# Sheet_power_1.net
KiCad netlist of a schematic drawn in Altium Designer
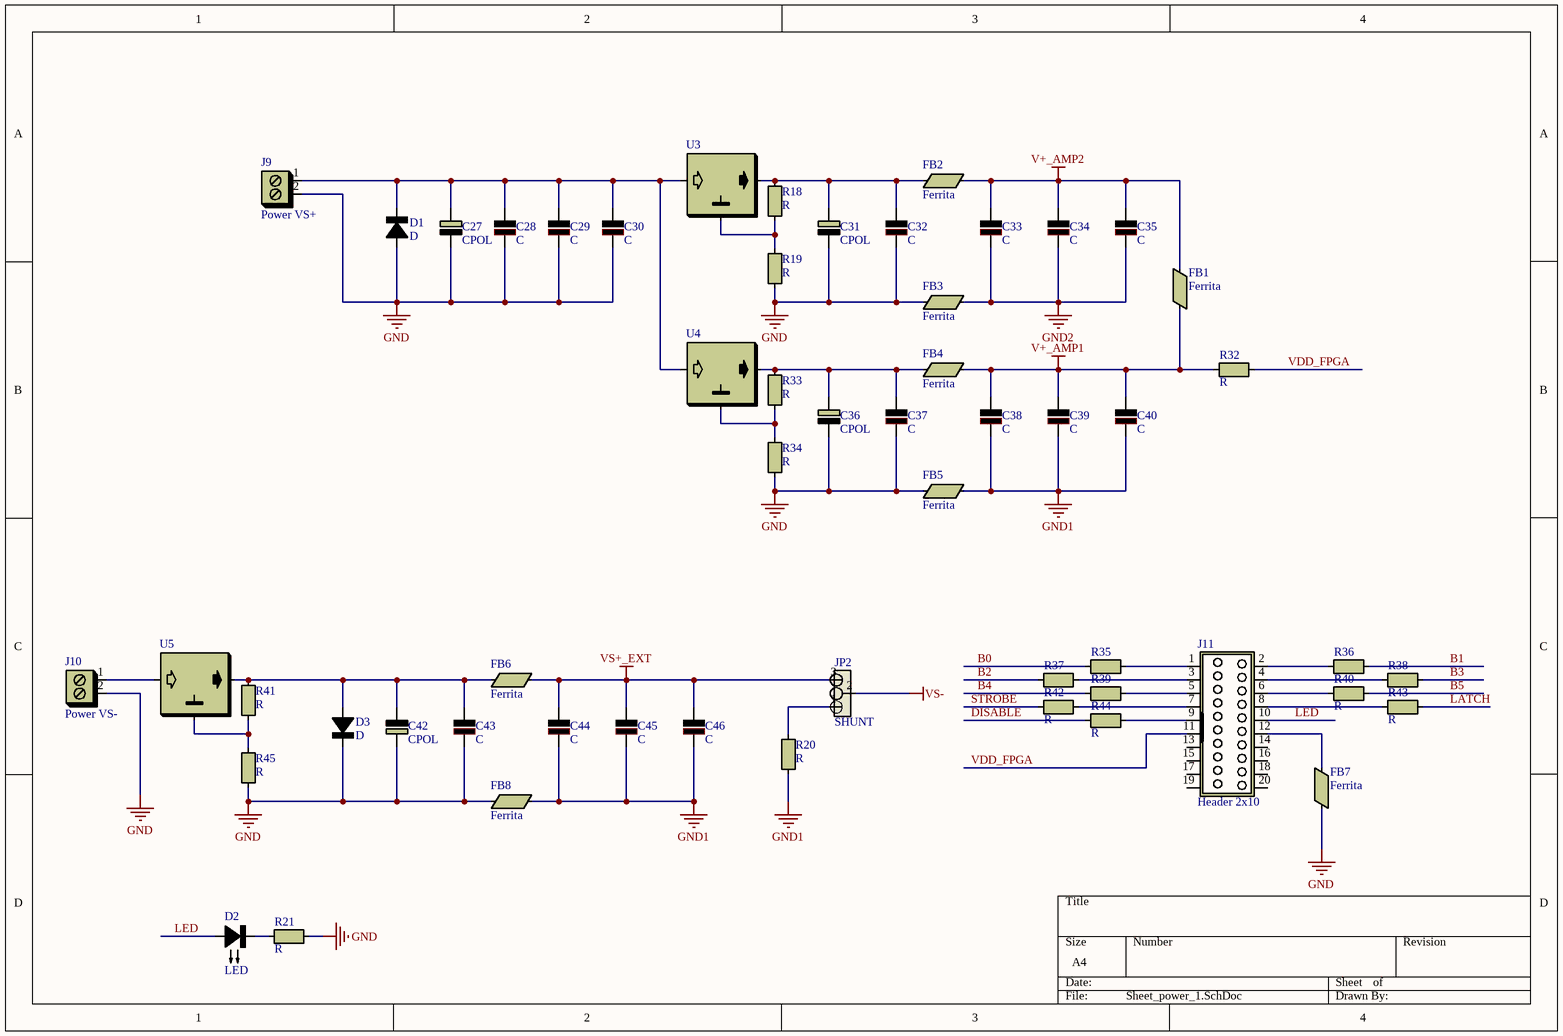
[diagram p0: Sheet_power_1.SchDoc]

(export (version "E")
  (design (tool "Eeschema 10.0.6"))
  (components
    (comp (ref "C27") (value "CPOL") (footprint "C_SMD_5.0 x 5.4") (libsource (lib "") (part "CPOL_1")))
    (comp (ref "C28") (value "C") (footprint "C_0805") (libsource (lib "Alberto_Sch") (part "C")))
    (comp (ref "C29") (value "C") (footprint "C_0805") (libsource (lib "Alberto_Sch") (part "C")))
    (comp (ref "C30") (value "C") (footprint "C_0805") (libsource (lib "Alberto_Sch") (part "C")))
    (comp (ref "C31") (value "CPOL") (footprint "C_SMD_5.0 x 5.4") (libsource (lib "") (part "CPOL_1")))
    (comp (ref "C32") (value "C") (footprint "C_0805") (libsource (lib "Alberto_Sch") (part "C")))
    (comp (ref "C33") (value "C") (footprint "C_0805") (libsource (lib "Alberto_Sch") (part "C")))
    (comp (ref "C34") (value "C") (footprint "C_0805") (libsource (lib "Alberto_Sch") (part "C")))
    (comp (ref "C35") (value "C") (footprint "C_0805") (libsource (lib "Alberto_Sch") (part "C")))
    (comp (ref "C36") (value "CPOL") (footprint "C_SMD_5.0 x 5.4") (libsource (lib "") (part "CPOL_1")))
    (comp (ref "C37") (value "C") (footprint "C_0805") (libsource (lib "Alberto_Sch") (part "C")))
    (comp (ref "C38") (value "C") (footprint "C_0805") (libsource (lib "Alberto_Sch") (part "C")))
    (comp (ref "C39") (value "C") (footprint "C_0805") (libsource (lib "Alberto_Sch") (part "C")))
    (comp (ref "C40") (value "C") (footprint "C_0805") (libsource (lib "Alberto_Sch") (part "C")))
    (comp (ref "C42")
      (value "CPOL")
      (footprint "C_SMD_5.0 x 5.4")
      (libsource (lib "Alberto_Sch") (part "CPOL"))
    )
    (comp (ref "C43") (value "C") (footprint "C_0805") (libsource (lib "Alberto_Sch") (part "C")))
    (comp (ref "C44") (value "C") (footprint "C_0805") (libsource (lib "Alberto_Sch") (part "C")))
    (comp (ref "C45") (value "C") (footprint "C_0805") (libsource (lib "Alberto_Sch") (part "C")))
    (comp (ref "C46") (value "C") (footprint "C_0805") (libsource (lib "Alberto_Sch") (part "C")))
    (comp (ref "D1") (value "D") (footprint "DZENER_0805") (libsource (lib "") (part "D_1")))
    (comp (ref "D2") (value "LED") (footprint "LED_0805") (libsource (lib "Alberto_Sch") (part "LED")))
    (comp (ref "D3") (value "D") (footprint "DZENER_0805") (libsource (lib "Alberto_Sch") (part "D")))
    (comp (ref "FB1") (value "Ferrita") (footprint "R_0805") (libsource (lib "Alberto_Sch") (part "Ferrita")))
    (comp (ref "FB2") (value "Ferrita") (footprint "R_0805") (libsource (lib "Alberto_Sch") (part "Ferrita")))
    (comp (ref "FB3") (value "Ferrita") (footprint "R_0805") (libsource (lib "Alberto_Sch") (part "Ferrita")))
    (comp (ref "FB4") (value "Ferrita") (footprint "R_0805") (libsource (lib "Alberto_Sch") (part "Ferrita")))
    (comp (ref "FB5") (value "Ferrita") (footprint "R_0805") (libsource (lib "Alberto_Sch") (part "Ferrita")))
    (comp (ref "FB6") (value "Ferrita") (footprint "R_0805") (libsource (lib "Alberto_Sch") (part "Ferrita")))
    (comp (ref "FB7") (value "Ferrita") (footprint "R_0805") (libsource (lib "Alberto_Sch") (part "Ferrita")))
    (comp (ref "FB8") (value "Ferrita") (footprint "R_0805") (libsource (lib "Alberto_Sch") (part "Ferrita")))
    (comp (ref "J9")
      (value "Power VS+")
      (footprint "Borna_PT_2")
      (libsource (lib "Alberto_Sch") (part "BORNA_2"))
    )
    (comp (ref "J10")
      (value "Power VS-")
      (footprint "Borna_PT_2")
      (libsource (lib "Alberto_Sch") (part "BORNA_2"))
    )
    (comp (ref "J11") (value "Header 2x10") (libsource (lib "Alberto_Sch") (part "Header 2x10")))
    (comp (ref "JP2")
      (value "SHUNT")
      (footprint "JUMPER_2,54_3")
      (libsource (lib "Alberto_Sch") (part "SHUNT"))
    )
    (comp (ref "R18") (value "R") (footprint "R_0603") (libsource (lib "Alberto_Sch") (part "R")))
    (comp (ref "R19") (value "R") (footprint "R_0603") (libsource (lib "Alberto_Sch") (part "R")))
    (comp (ref "R20") (value "R") (footprint "R_0603") (libsource (lib "Alberto_Sch") (part "R")))
    (comp (ref "R21") (value "R") (footprint "R_0603") (libsource (lib "") (part "R_1")))
    (comp (ref "R32") (value "R") (footprint "R_0603") (libsource (lib "") (part "R_1")))
    (comp (ref "R33") (value "R") (footprint "R_0603") (libsource (lib "Alberto_Sch") (part "R")))
    (comp (ref "R34") (value "R") (footprint "R_0603") (libsource (lib "Alberto_Sch") (part "R")))
    (comp (ref "R35") (value "R") (footprint "R_0603") (libsource (lib "") (part "R_1")))
    (comp (ref "R36") (value "R") (footprint "R_0603") (libsource (lib "") (part "R_1")))
    (comp (ref "R37") (value "R") (footprint "R_0603") (libsource (lib "") (part "R_1")))
    (comp (ref "R38") (value "R") (footprint "R_0603") (libsource (lib "") (part "R_1")))
    (comp (ref "R39") (value "R") (footprint "R_0603") (libsource (lib "") (part "R_1")))
    (comp (ref "R40") (value "R") (footprint "R_0603") (libsource (lib "") (part "R_1")))
    (comp (ref "R41") (value "R") (footprint "R_0603") (libsource (lib "Alberto_Sch") (part "R")))
    (comp (ref "R42") (value "R") (footprint "R_0603") (libsource (lib "") (part "R_1")))
    (comp (ref "R43") (value "R") (footprint "R_0603") (libsource (lib "") (part "R_1")))
    (comp (ref "R44") (value "R") (footprint "R_0603") (libsource (lib "") (part "R_1")))
    (comp (ref "R45") (value "R") (footprint "R_0603") (libsource (lib "Alberto_Sch") (part "R")))
    (comp (ref "U3")
      (value "VOLTAGE_REGULATOR_3")
      (footprint "REG_DPAK")
      (libsource (lib "Alberto_Sch") (part "VOLTAGE_REGULATOR_3"))
    )
    (comp (ref "U4")
      (value "VOLTAGE_REGULATOR_3")
      (footprint "REG_DPAK")
      (libsource (lib "Alberto_Sch") (part "VOLTAGE_REGULATOR_3"))
    )
    (comp (ref "U5")
      (value "VOLTAGE_REGULATOR_3")
      (footprint "REG_DPAK")
      (libsource (lib "Alberto_Sch") (part "VOLTAGE_REGULATOR_3"))
    )
  )
  (nets
    (net (code "1") (name "/B0") (class "Default") (node (ref "R35") (pin "1") (pintype "passive")))
    (net (code "2") (name "/B1") (class "Default") (node (ref "R36") (pin "2") (pintype "passive")))
    (net (code "3") (name "/B2") (class "Default") (node (ref "R37") (pin "1") (pintype "passive")))
    (net (code "4") (name "/B3") (class "Default") (node (ref "R38") (pin "2") (pintype "passive")))
    (net (code "5") (name "/B4") (class "Default") (node (ref "R39") (pin "1") (pintype "passive")))
    (net (code "6") (name "/B5") (class "Default") (node (ref "R40") (pin "2") (pintype "passive")))
    (net (code "7") (name "/LATCH") (class "Default") (node (ref "R43") (pin "2") (pintype "passive")))
    (net (code "8") (name "/LED") (class "Default")
      (node (ref "D2") (pin "A") (pintype "passive"))
      (node (ref "J11") (pin "10") (pinfunction "10_10") (pintype "passive"))
    )
    (net (code "9") (name "/STROBE") (class "Default") (node (ref "R42") (pin "1") (pintype "passive")))
    (net (code "10") (name "/VDD_FPGA") (class "Default")
      (node (ref "J11") (pin "11") (pinfunction "11_11") (pintype "passive"))
      (node (ref "R32") (pin "2") (pintype "passive"))
    )
    (net (code "11") (name "/~{DISABLE}") (class "Default") (node (ref "R44") (pin "1") (pintype "passive")))
    (net (code "12") (name "GND") (class "Default")
      (node (ref "C27") (pin "1") (pintype "passive"))
      (node (ref "C28") (pin "2") (pintype "passive"))
      (node (ref "C29") (pin "2") (pintype "passive"))
      (node (ref "C30") (pin "2") (pintype "passive"))
      (node (ref "C31") (pin "1") (pintype "passive"))
      (node (ref "C32") (pin "2") (pintype "passive"))
      (node (ref "C36") (pin "1") (pintype "passive"))
      (node (ref "C37") (pin "2") (pintype "passive"))
      (node (ref "C42") (pin "2") (pintype "passive"))
      (node (ref "C43") (pin "2") (pintype "passive"))
      (node (ref "D1") (pin "A") (pintype "passive"))
      (node (ref "D3") (pin "K") (pintype "passive"))
      (node (ref "FB3") (pin "2") (pintype "passive"))
      (node (ref "FB5") (pin "2") (pintype "passive"))
      (node (ref "FB7") (pin "1") (pintype "passive"))
      (node (ref "FB8") (pin "2") (pintype "passive"))
      (node (ref "J10") (pin "2") (pintype "passive"))
      (node (ref "J9") (pin "2") (pintype "passive"))
      (node (ref "R19") (pin "2") (pintype "passive"))
      (node (ref "R21") (pin "2") (pintype "passive"))
      (node (ref "R34") (pin "2") (pintype "passive"))
      (node (ref "R45") (pin "2") (pintype "passive"))
    )
    (net (code "13") (name "GND1") (class "Default")
      (node (ref "C38") (pin "2") (pintype "passive"))
      (node (ref "C39") (pin "2") (pintype "passive"))
      (node (ref "C40") (pin "2") (pintype "passive"))
      (node (ref "C44") (pin "2") (pintype "passive"))
      (node (ref "C45") (pin "2") (pintype "passive"))
      (node (ref "C46") (pin "2") (pintype "passive"))
      (node (ref "FB5") (pin "1") (pintype "passive"))
      (node (ref "FB8") (pin "1") (pintype "passive"))
      (node (ref "R20") (pin "2") (pintype "passive"))
    )
    (net (code "14") (name "GND2") (class "Default")
      (node (ref "C33") (pin "2") (pintype "passive"))
      (node (ref "C34") (pin "2") (pintype "passive"))
      (node (ref "C35") (pin "2") (pintype "passive"))
      (node (ref "FB3") (pin "1") (pintype "passive"))
    )
    (net (code "15") (name "Net-(C27-Pad2)") (class "Default")
      (node (ref "C27") (pin "2") (pintype "passive"))
      (node (ref "C28") (pin "1") (pintype "passive"))
      (node (ref "C29") (pin "1") (pintype "passive"))
      (node (ref "C30") (pin "1") (pintype "passive"))
      (node (ref "D1") (pin "K") (pintype "passive"))
      (node (ref "J9") (pin "1") (pintype "passive"))
      (node (ref "U3") (pin "IN") (pintype "passive"))
      (node (ref "U4") (pin "IN") (pintype "passive"))
    )
    (net (code "16") (name "Net-(C31-Pad2)") (class "Default")
      (node (ref "C31") (pin "2") (pintype "passive"))
      (node (ref "C32") (pin "1") (pintype "passive"))
      (node (ref "FB2") (pin "2") (pintype "passive"))
      (node (ref "R18") (pin "1") (pintype "passive"))
      (node (ref "U3") (pin "OUT") (pintype "passive"))
    )
    (net (code "17") (name "Net-(C36-Pad2)") (class "Default")
      (node (ref "C36") (pin "2") (pintype "passive"))
      (node (ref "C37") (pin "1") (pintype "passive"))
      (node (ref "FB4") (pin "2") (pintype "passive"))
      (node (ref "R33") (pin "1") (pintype "passive"))
      (node (ref "U4") (pin "OUT") (pintype "passive"))
    )
    (net (code "18") (name "Net-(C42-Pad1)") (class "Default")
      (node (ref "C42") (pin "1") (pintype "passive"))
      (node (ref "C43") (pin "1") (pintype "passive"))
      (node (ref "D3") (pin "A") (pintype "passive"))
      (node (ref "FB6") (pin "2") (pintype "passive"))
      (node (ref "R41") (pin "1") (pintype "passive"))
      (node (ref "U5") (pin "OUT") (pintype "passive"))
    )
    (net (code "19") (name "Net-(D2-PadK)") (class "Default")
      (node (ref "D2") (pin "K") (pintype "passive"))
      (node (ref "R21") (pin "1") (pintype "passive"))
    )
    (net (code "20") (name "Net-(FB7-Pad2)") (class "Default")
      (node (ref "FB7") (pin "2") (pintype "passive"))
      (node (ref "J11") (pin "12") (pinfunction "12_12") (pintype "passive"))
    )
    (net (code "21") (name "Net-(J10-Pad1)") (class "Default")
      (node (ref "J10") (pin "1") (pintype "passive"))
      (node (ref "U5") (pin "IN") (pintype "passive"))
    )
    (net (code "22") (name "Net-(J11-Pad1)") (class "Default")
      (node (ref "J11") (pin "1") (pinfunction "1_1") (pintype "passive"))
      (node (ref "R35") (pin "2") (pintype "passive"))
    )
    (net (code "23") (name "Net-(J11-Pad2)") (class "Default")
      (node (ref "J11") (pin "2") (pinfunction "2_2") (pintype "passive"))
      (node (ref "R36") (pin "1") (pintype "passive"))
    )
    (net (code "24") (name "Net-(J11-Pad3)") (class "Default")
      (node (ref "J11") (pin "3") (pinfunction "3_3") (pintype "passive"))
      (node (ref "R37") (pin "2") (pintype "passive"))
    )
    (net (code "25") (name "Net-(J11-Pad4)") (class "Default")
      (node (ref "J11") (pin "4") (pinfunction "4_4") (pintype "passive"))
      (node (ref "R38") (pin "1") (pintype "passive"))
    )
    (net (code "26") (name "Net-(J11-Pad5)") (class "Default")
      (node (ref "J11") (pin "5") (pinfunction "5_5") (pintype "passive"))
      (node (ref "R39") (pin "2") (pintype "passive"))
    )
    (net (code "27") (name "Net-(J11-Pad6)") (class "Default")
      (node (ref "J11") (pin "6") (pinfunction "6_6") (pintype "passive"))
      (node (ref "R40") (pin "1") (pintype "passive"))
    )
    (net (code "28") (name "Net-(J11-Pad7)") (class "Default")
      (node (ref "J11") (pin "7") (pinfunction "7_7") (pintype "passive"))
      (node (ref "R42") (pin "2") (pintype "passive"))
    )
    (net (code "29") (name "Net-(J11-Pad8)") (class "Default")
      (node (ref "J11") (pin "8") (pinfunction "8_8") (pintype "passive"))
      (node (ref "R43") (pin "1") (pintype "passive"))
    )
    (net (code "30") (name "Net-(J11-Pad9)") (class "Default")
      (node (ref "J11") (pin "9") (pinfunction "9_9") (pintype "passive"))
      (node (ref "R44") (pin "2") (pintype "passive"))
    )
    (net (code "31") (name "Net-(JP2-Pad1)") (class "Default")
      (node (ref "JP2") (pin "1") (pinfunction "1_1") (pintype "passive"))
      (node (ref "R20") (pin "1") (pintype "passive"))
    )
    (net (code "32") (name "Net-(R18-Pad2)") (class "Default")
      (node (ref "R18") (pin "2") (pintype "passive"))
      (node (ref "R19") (pin "1") (pintype "passive"))
      (node (ref "U3") (pin "GND") (pintype "passive"))
    )
    (net (code "33") (name "Net-(R33-Pad2)") (class "Default")
      (node (ref "R33") (pin "2") (pintype "passive"))
      (node (ref "R34") (pin "1") (pintype "passive"))
      (node (ref "U4") (pin "GND") (pintype "passive"))
    )
    (net (code "34") (name "Net-(R41-Pad2)") (class "Default")
      (node (ref "R41") (pin "2") (pintype "passive"))
      (node (ref "R45") (pin "1") (pintype "passive"))
      (node (ref "U5") (pin "GND") (pintype "passive"))
    )
    (net (code "35") (name "V+_AMP1") (class "Default")
      (node (ref "C38") (pin "1") (pintype "passive"))
      (node (ref "C39") (pin "1") (pintype "passive"))
      (node (ref "C40") (pin "1") (pintype "passive"))
      (node (ref "FB1") (pin "1") (pintype "passive"))
      (node (ref "FB4") (pin "1") (pintype "passive"))
      (node (ref "R32") (pin "1") (pintype "passive"))
    )
    (net (code "36") (name "V+_AMP2") (class "Default")
      (node (ref "C33") (pin "1") (pintype "passive"))
      (node (ref "C34") (pin "1") (pintype "passive"))
      (node (ref "C35") (pin "1") (pintype "passive"))
      (node (ref "FB1") (pin "2") (pintype "passive"))
      (node (ref "FB2") (pin "1") (pintype "passive"))
    )
    (net (code "37") (name "VS+_EXT") (class "Default")
      (node (ref "C44") (pin "1") (pintype "passive"))
      (node (ref "C45") (pin "1") (pintype "passive"))
      (node (ref "C46") (pin "1") (pintype "passive"))
      (node (ref "FB6") (pin "1") (pintype "passive"))
      (node (ref "JP2") (pin "3") (pinfunction "3_3") (pintype "passive"))
    )
    (net (code "38") (name "VS-") (class "Default")
      (node (ref "JP2") (pin "2") (pinfunction "2_2") (pintype "passive"))
    )
    (net (code "39") (name "unconnected-(J11-Pad13)") (class "Default")
      (node (ref "J11") (pin "13") (pinfunction "13_13") (pintype "passive"))
    )
    (net (code "40") (name "unconnected-(J11-Pad14)") (class "Default")
      (node (ref "J11") (pin "14") (pinfunction "14_14") (pintype "passive"))
    )
    (net (code "41") (name "unconnected-(J11-Pad15)") (class "Default")
      (node (ref "J11") (pin "15") (pinfunction "15_15") (pintype "passive"))
    )
    (net (code "42") (name "unconnected-(J11-Pad16)") (class "Default")
      (node (ref "J11") (pin "16") (pinfunction "16_16") (pintype "passive"))
    )
    (net (code "43") (name "unconnected-(J11-Pad17)") (class "Default")
      (node (ref "J11") (pin "17") (pinfunction "17_17") (pintype "passive"))
    )
    (net (code "44") (name "unconnected-(J11-Pad18)") (class "Default")
      (node (ref "J11") (pin "18") (pinfunction "18_18") (pintype "passive"))
    )
    (net (code "45") (name "unconnected-(J11-Pad19)") (class "Default")
      (node (ref "J11") (pin "19") (pinfunction "19_19") (pintype "passive"))
    )
    (net (code "46") (name "unconnected-(J11-Pad20)") (class "Default")
      (node (ref "J11") (pin "20") (pinfunction "20_20") (pintype "passive"))
    )
  )
)
